# module_rev2.net
KiCad netlist of a schematic drawn in Altium Designer
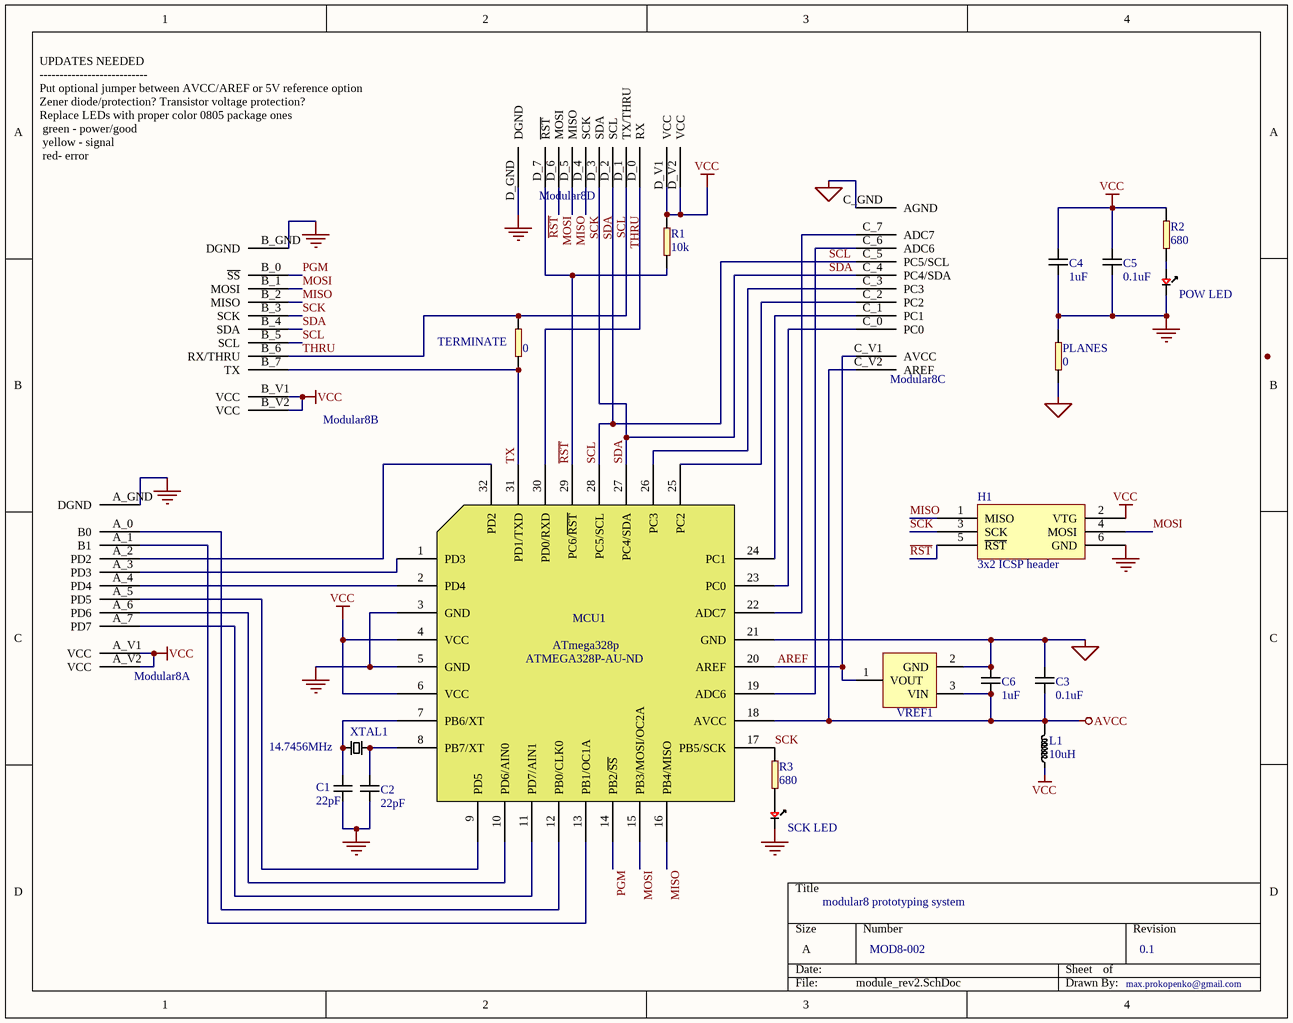
[diagram p0: module_rev2.SchDoc]

(export (version "E")
  (design (tool "Eeschema 10.0.6"))
  (components
    (comp (ref "C1")
      (value "C 22pF 25V")
      (footprint "0603")
      (fields (field (name "C") "22pF"))
      (libsource (lib "RLC") (part "C 22pF 25V"))
    )
    (comp (ref "C2")
      (value "C 22pF 25V")
      (footprint "0603")
      (fields (field (name "C") "22pF"))
      (libsource (lib "") (part "C 22pF 25V_1"))
    )
    (comp (ref "C3")
      (value "C 0.1uF 25V")
      (footprint "0603")
      (fields (field (name "C") "0.1uF"))
      (libsource (lib "RLC") (part "C 0.1uF 25V"))
    )
    (comp (ref "C4")
      (value "C 1uF 25V")
      (footprint "0603")
      (fields (field (name "C") "1uF"))
      (libsource (lib "RLC") (part "C 1uF 25V"))
    )
    (comp (ref "C5")
      (value "C 0.1uF 25V")
      (footprint "0603")
      (fields (field (name "C") "0.1uF"))
      (libsource (lib "RLC") (part "C 0.1uF 25V"))
    )
    (comp (ref "C6")
      (value "C 1uF 25V")
      (footprint "0603")
      (fields (field (name "C") "1uF"))
      (libsource (lib "RLC") (part "C 1uF 25V"))
    )
    (comp (ref "H1")
      (value "3x2 ICSP header")
      (footprint "3x2 THRU HOLES 0.1\" PITCH")
      (libsource (lib "OpBots") (part "3x2 ICSP header"))
    )
    (comp (ref "L1")
      (value "L 10uH")
      (footprint "0603")
      (fields (field (name "L") "10uH"))
      (libsource (lib "RLC") (part "L 10uH"))
    )
    (comp (ref "MCU1")
      (value "ATmega328p")
      (footprint "ATmega328p TQFP")
      (fields (field (name "SUPPLIER PART NUMBER 1") "ATMEGA328P-AU-ND"))
      (libsource (lib "OpBots") (part "ATmega328p"))
    )
    (comp (ref "Modular8")
      (value "modular8_rev2")
      (footprint "modular8 metric")
      (libsource (lib "OpBots") (part "modular8_rev2"))
    )
    (comp (ref "PLANES")
      (value "R 0")
      (footprint "0603")
      (fields (field (name "R") "0"))
      (libsource (lib "") (part "R 0_1"))
    )
    (comp (ref "POW LED") (value "LEDG") (footprint "0805 - LED") (libsource (lib "OpBots") (part "LEDG")))
    (comp (ref "R1")
      (value "R 10k")
      (footprint "0603")
      (fields (field (name "R") "10k"))
      (libsource (lib "RLC") (part "R 10k"))
    )
    (comp (ref "R2")
      (value "R 680")
      (footprint "0603")
      (fields (field (name "R") "680"))
      (libsource (lib "RLC") (part "R 680"))
    )
    (comp (ref "R3")
      (value "R 680")
      (footprint "0603")
      (fields (field (name "R") "680"))
      (libsource (lib "RLC") (part "R 680"))
    )
    (comp (ref "SCK LED") (value "LEDY") (footprint "0805 - LED") (libsource (lib "OpBots") (part "LEDY")))
    (comp (ref "TERMINATE")
      (value "R 0")
      (footprint "0603")
      (fields (field (name "R") "0"))
      (libsource (lib "RLC") (part "R 0"))
    )
    (comp (ref "VREF1")
      (value "AD1584BRTZ")
      (footprint "SOT-23-3")
      (libsource (lib "OpBots") (part "AD1584BRTZ"))
    )
    (comp (ref "XTAL1")
      (value "XTAL 14.7456MHz")
      (footprint "XTAL CSM-3X")
      (fields (field (name "FREQUENCY") "14.7456MHz"))
      (libsource (lib "OpBots") (part "XTAL 14.7456MHz"))
    )
  )
  (nets
    (net (code "1") (name "/AREF") (class "Default")
      (node (ref "MCU1") (pin "20") (pinfunction "AREF_20") (pintype "passive"))
      (node (ref "Modular8") (pin "C_V1") (pinfunction "AVCC_C_V1") (pintype "passive"))
      (node (ref "VREF1") (pin "1") (pinfunction "VOUT_1") (pintype "passive"))
    )
    (net (code "2") (name "/MISO") (class "Default")
      (node (ref "H1") (pin "1") (pinfunction "MISO_1") (pintype "passive"))
      (node (ref "MCU1") (pin "16") (pinfunction "PB4/MISO_16") (pintype "passive"))
      (node (ref "Modular8") (pin "B_2") (pinfunction "MISO_B_2") (pintype "passive"))
      (node (ref "Modular8") (pin "D_5") (pinfunction "MISO_D_5") (pintype "passive"))
    )
    (net (code "3") (name "/MOSI") (class "Default")
      (node (ref "H1") (pin "4") (pinfunction "MOSI_4") (pintype "passive"))
      (node (ref "MCU1") (pin "15") (pinfunction "PB3/MOSI/OC2A_15") (pintype "passive"))
      (node (ref "Modular8") (pin "B_1") (pinfunction "MOSI_B_1") (pintype "passive"))
      (node (ref "Modular8") (pin "D_6") (pinfunction "MOSI_D_6") (pintype "passive"))
    )
    (net (code "4") (name "/PGM") (class "Default")
      (node (ref "MCU1") (pin "14") (pinfunction "PB2/~{SS}_14") (pintype "passive"))
      (node (ref "Modular8") (pin "B_0") (pinfunction "~{SS}_B_0") (pintype "passive"))
    )
    (net (code "5") (name "/SCK") (class "Default")
      (node (ref "H1") (pin "3") (pinfunction "SCK_3") (pintype "passive"))
      (node (ref "MCU1") (pin "17") (pinfunction "PB5/SCK_17") (pintype "passive"))
      (node (ref "Modular8") (pin "B_3") (pinfunction "SCK_B_3") (pintype "passive"))
      (node (ref "Modular8") (pin "D_4") (pinfunction "SCK_D_4") (pintype "passive"))
      (node (ref "R3") (pin "1") (pintype "passive"))
    )
    (net (code "6") (name "/SCL") (class "Default")
      (node (ref "MCU1") (pin "28") (pinfunction "PC5/SCL_28") (pintype "passive"))
      (node (ref "Modular8") (pin "B_5") (pinfunction "SCL_B_5") (pintype "passive"))
      (node (ref "Modular8") (pin "C_5") (pinfunction "PC5/SCL_C_5") (pintype "passive"))
      (node (ref "Modular8") (pin "D_2") (pinfunction "SCL_D_2") (pintype "passive"))
    )
    (net (code "7") (name "/SDA") (class "Default")
      (node (ref "MCU1") (pin "27") (pinfunction "PC4/SDA_27") (pintype "passive"))
      (node (ref "Modular8") (pin "B_4") (pinfunction "SDA_B_4") (pintype "passive"))
      (node (ref "Modular8") (pin "C_4") (pinfunction "PC4/SDA_C_4") (pintype "passive"))
      (node (ref "Modular8") (pin "D_3") (pinfunction "SDA_D_3") (pintype "passive"))
    )
    (net (code "8") (name "/THRU") (class "Default")
      (node (ref "Modular8") (pin "B_6") (pinfunction "RX/THRU_B_6") (pintype "passive"))
      (node (ref "Modular8") (pin "D_1") (pinfunction "TX/THRU_D_1") (pintype "passive"))
      (node (ref "TERMINATE") (pin "1") (pintype "passive"))
    )
    (net (code "9") (name "/TX") (class "Default")
      (node (ref "MCU1") (pin "31") (pinfunction "PD1/TXD_31") (pintype "passive"))
      (node (ref "Modular8") (pin "B_7") (pinfunction "TX_B_7") (pintype "passive"))
      (node (ref "TERMINATE") (pin "2") (pintype "passive"))
    )
    (net (code "10") (name "/~{RST}") (class "Default")
      (node (ref "H1") (pin "5") (pinfunction "~{RST}_5") (pintype "passive"))
      (node (ref "MCU1") (pin "29") (pinfunction "PC6/~{RST}_29") (pintype "passive"))
      (node (ref "Modular8") (pin "D_7") (pinfunction "~{RST}_D_7") (pintype "passive"))
      (node (ref "R1") (pin "2") (pintype "passive"))
    )
    (net (code "11") (name "AGND") (class "Default")
      (node (ref "C3") (pin "1") (pintype "passive"))
      (node (ref "C6") (pin "1") (pintype "passive"))
      (node (ref "MCU1") (pin "21") (pinfunction "GND_21") (pintype "passive"))
      (node (ref "Modular8") (pin "C_GND") (pinfunction "AGND_C_GND") (pintype "passive"))
      (node (ref "PLANES") (pin "1") (pintype "passive"))
      (node (ref "VREF1") (pin "2") (pinfunction "GND_2") (pintype "passive"))
    )
    (net (code "12") (name "AVCC") (class "Default")
      (node (ref "C3") (pin "2") (pintype "passive"))
      (node (ref "C6") (pin "2") (pintype "passive"))
      (node (ref "L1") (pin "1") (pintype "passive"))
      (node (ref "MCU1") (pin "18") (pinfunction "AVCC_18") (pintype "passive"))
      (node (ref "Modular8") (pin "C_V2") (pinfunction "AREF_C_V2") (pintype "passive"))
      (node (ref "VREF1") (pin "3") (pinfunction "VIN_3") (pintype "passive"))
    )
    (net (code "13") (name "DGND") (class "Default")
      (node (ref "C1") (pin "1") (pintype "passive"))
      (node (ref "C2") (pin "2") (pintype "passive"))
      (node (ref "C4") (pin "2") (pintype "passive"))
      (node (ref "C5") (pin "2") (pintype "passive"))
      (node (ref "H1") (pin "6") (pinfunction "GND_6") (pintype "passive"))
      (node (ref "MCU1") (pin "3") (pinfunction "GND_3") (pintype "passive"))
      (node (ref "MCU1") (pin "5") (pinfunction "GND_5") (pintype "passive"))
      (node (ref "Modular8") (pin "A_GND") (pinfunction "DGND_A_GND") (pintype "passive"))
      (node (ref "Modular8") (pin "B_GND") (pinfunction "DGND_B_GND") (pintype "passive"))
      (node (ref "Modular8") (pin "D_GND") (pinfunction "DGND_D_GND") (pintype "passive"))
      (node (ref "PLANES") (pin "2") (pintype "passive"))
      (node (ref "POW LED") (pin "2") (pinfunction "K_2") (pintype "passive"))
      (node (ref "SCK LED") (pin "1") (pinfunction "K_1") (pintype "passive"))
    )
    (net (code "14") (name "Net-(MCU1-ADC6)") (class "Default")
      (node (ref "MCU1") (pin "19") (pinfunction "ADC6_19") (pintype "passive"))
      (node (ref "Modular8") (pin "C_6") (pinfunction "ADC6_C_6") (pintype "passive"))
    )
    (net (code "15") (name "Net-(MCU1-ADC7)") (class "Default")
      (node (ref "MCU1") (pin "22") (pinfunction "ADC7_22") (pintype "passive"))
      (node (ref "Modular8") (pin "C_7") (pinfunction "ADC7_C_7") (pintype "passive"))
    )
    (net (code "16") (name "Net-(MCU1-PB0{slash}CLK0)") (class "Default")
      (node (ref "MCU1") (pin "12") (pinfunction "PB0/CLK0_12") (pintype "passive"))
      (node (ref "Modular8") (pin "A_0") (pinfunction "B0_A_0") (pintype "passive"))
    )
    (net (code "17") (name "Net-(MCU1-PB1{slash}OC1A)") (class "Default")
      (node (ref "MCU1") (pin "13") (pinfunction "PB1/OC1A_13") (pintype "passive"))
      (node (ref "Modular8") (pin "A_1") (pinfunction "B1_A_1") (pintype "passive"))
    )
    (net (code "18") (name "Net-(MCU1-PB6{slash}XT)") (class "Default")
      (node (ref "C1") (pin "2") (pintype "passive"))
      (node (ref "MCU1") (pin "7") (pinfunction "PB6/XT_7") (pintype "passive"))
      (node (ref "XTAL1") (pin "1") (pintype "passive"))
    )
    (net (code "19") (name "Net-(MCU1-PB7{slash}XT)") (class "Default")
      (node (ref "C2") (pin "1") (pintype "passive"))
      (node (ref "MCU1") (pin "8") (pinfunction "PB7/XT_8") (pintype "passive"))
      (node (ref "XTAL1") (pin "2") (pintype "passive"))
    )
    (net (code "20") (name "Net-(MCU1-PC0)") (class "Default")
      (node (ref "MCU1") (pin "23") (pinfunction "PC0_23") (pintype "passive"))
      (node (ref "Modular8") (pin "C_0") (pinfunction "PC0_C_0") (pintype "passive"))
    )
    (net (code "21") (name "Net-(MCU1-PC1)") (class "Default")
      (node (ref "MCU1") (pin "24") (pinfunction "PC1_24") (pintype "passive"))
      (node (ref "Modular8") (pin "C_1") (pinfunction "PC1_C_1") (pintype "passive"))
    )
    (net (code "22") (name "Net-(MCU1-PC2)") (class "Default")
      (node (ref "MCU1") (pin "25") (pinfunction "PC2_25") (pintype "passive"))
      (node (ref "Modular8") (pin "C_2") (pinfunction "PC2_C_2") (pintype "passive"))
    )
    (net (code "23") (name "Net-(MCU1-PC3)") (class "Default")
      (node (ref "MCU1") (pin "26") (pinfunction "PC3_26") (pintype "passive"))
      (node (ref "Modular8") (pin "C_3") (pinfunction "PC3_C_3") (pintype "passive"))
    )
    (net (code "24") (name "Net-(MCU1-PD0{slash}RXD)") (class "Default")
      (node (ref "MCU1") (pin "30") (pinfunction "PD0/RXD_30") (pintype "passive"))
      (node (ref "Modular8") (pin "D_0") (pinfunction "RX_D_0") (pintype "passive"))
    )
    (net (code "25") (name "Net-(MCU1-PD2)") (class "Default")
      (node (ref "MCU1") (pin "32") (pinfunction "PD2_32") (pintype "passive"))
      (node (ref "Modular8") (pin "A_2") (pinfunction "PD2_A_2") (pintype "passive"))
    )
    (net (code "26") (name "Net-(MCU1-PD3)") (class "Default")
      (node (ref "MCU1") (pin "1") (pinfunction "PD3_1") (pintype "passive"))
      (node (ref "Modular8") (pin "A_3") (pinfunction "PD3_A_3") (pintype "passive"))
    )
    (net (code "27") (name "Net-(MCU1-PD4)") (class "Default")
      (node (ref "MCU1") (pin "2") (pinfunction "PD4_2") (pintype "passive"))
      (node (ref "Modular8") (pin "A_4") (pinfunction "PD4_A_4") (pintype "passive"))
    )
    (net (code "28") (name "Net-(MCU1-PD5)") (class "Default")
      (node (ref "MCU1") (pin "9") (pinfunction "PD5_9") (pintype "passive"))
      (node (ref "Modular8") (pin "A_5") (pinfunction "PD5_A_5") (pintype "passive"))
    )
    (net (code "29") (name "Net-(MCU1-PD6{slash}AIN0)") (class "Default")
      (node (ref "MCU1") (pin "10") (pinfunction "PD6/AIN0_10") (pintype "passive"))
      (node (ref "Modular8") (pin "A_6") (pinfunction "PD6_A_6") (pintype "passive"))
    )
    (net (code "30") (name "Net-(MCU1-PD7{slash}AIN1)") (class "Default")
      (node (ref "MCU1") (pin "11") (pinfunction "PD7/AIN1_11") (pintype "passive"))
      (node (ref "Modular8") (pin "A_7") (pinfunction "PD7_A_7") (pintype "passive"))
    )
    (net (code "31") (name "Net-(POW LED-A)") (class "Default")
      (node (ref "POW LED") (pin "1") (pinfunction "A_1") (pintype "passive"))
      (node (ref "R2") (pin "2") (pintype "passive"))
    )
    (net (code "32") (name "Net-(SCK LED-A)") (class "Default")
      (node (ref "R3") (pin "2") (pintype "passive"))
      (node (ref "SCK LED") (pin "2") (pinfunction "A_2") (pintype "passive"))
    )
    (net (code "33") (name "VCC") (class "Default")
      (node (ref "C4") (pin "1") (pintype "passive"))
      (node (ref "C5") (pin "1") (pintype "passive"))
      (node (ref "H1") (pin "2") (pinfunction "VTG_2") (pintype "passive"))
      (node (ref "L1") (pin "2") (pintype "passive"))
      (node (ref "MCU1") (pin "4") (pinfunction "VCC_4") (pintype "passive"))
      (node (ref "MCU1") (pin "6") (pinfunction "VCC_6") (pintype "passive"))
      (node (ref "Modular8") (pin "A_V1") (pinfunction "VCC_A_V1") (pintype "passive"))
      (node (ref "Modular8") (pin "A_V2") (pinfunction "VCC_A_V2") (pintype "passive"))
      (node (ref "Modular8") (pin "B_V1") (pinfunction "VCC_B_V1") (pintype "passive"))
      (node (ref "Modular8") (pin "B_V2") (pinfunction "VCC_B_V2") (pintype "passive"))
      (node (ref "Modular8") (pin "D_V1") (pinfunction "VCC_D_V1") (pintype "passive"))
      (node (ref "Modular8") (pin "D_V2") (pinfunction "VCC_D_V2") (pintype "passive"))
      (node (ref "R1") (pin "1") (pintype "passive"))
      (node (ref "R2") (pin "1") (pintype "passive"))
    )
  )
)
